# 1_RPi.net
KiCad netlist of a schematic drawn in Altium Designer
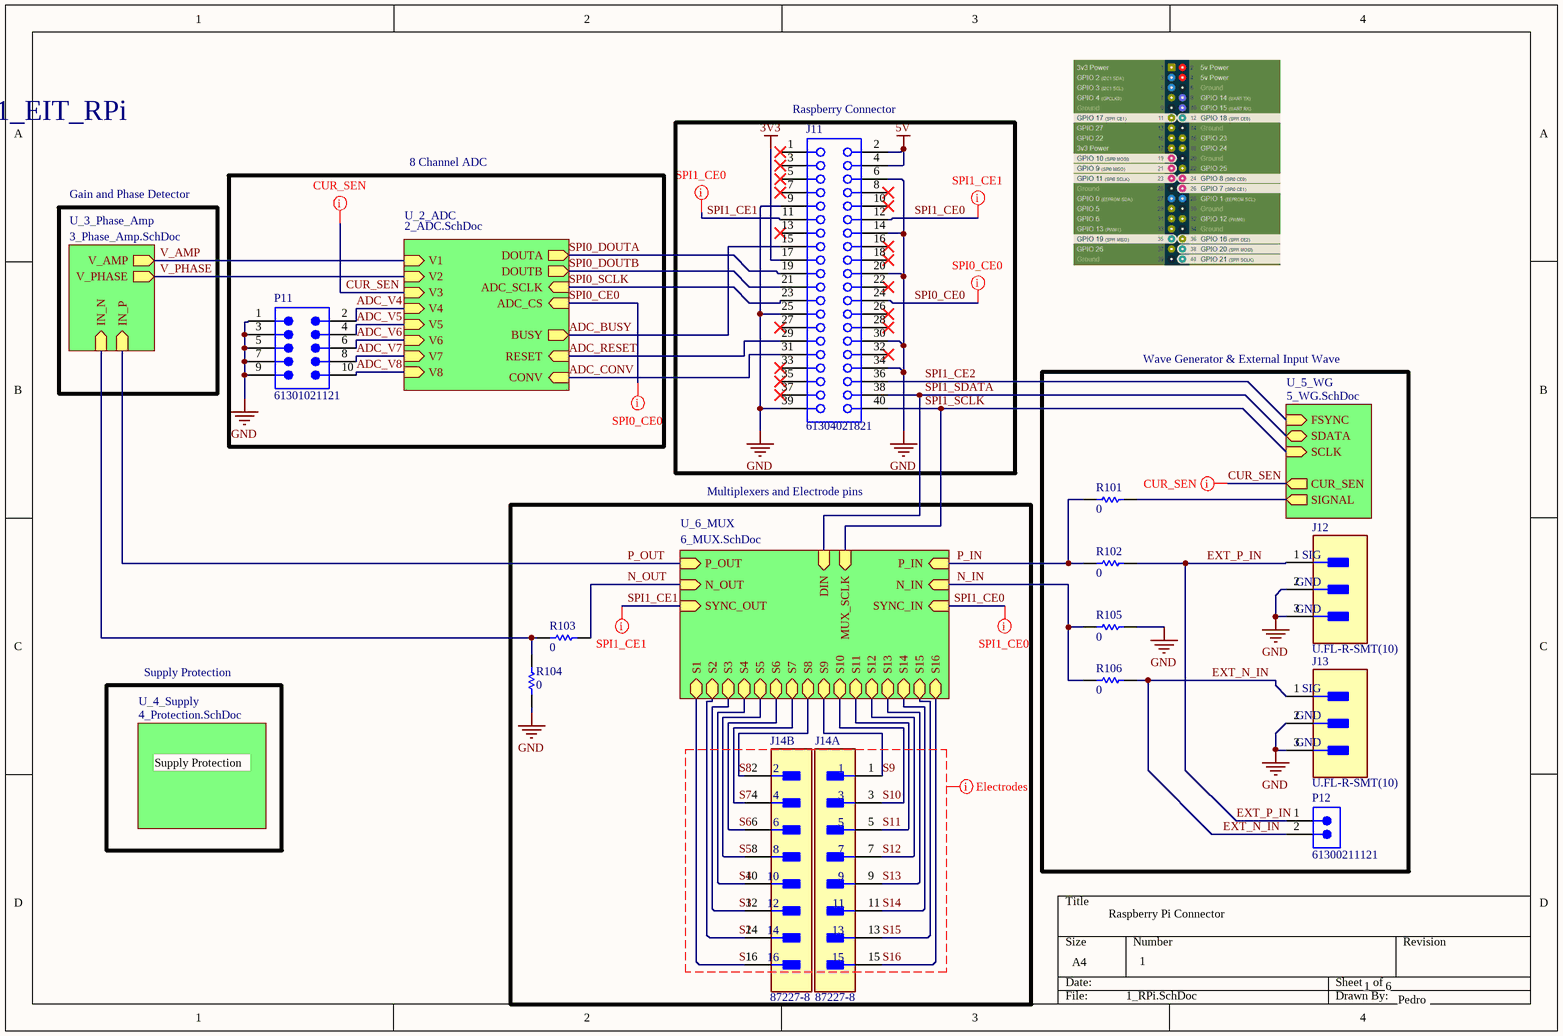
[diagram p0: 1_RPi.SchDoc]

(export (version "E")
  (design (tool "Eeschema 10.0.6"))
  (components
    (comp (ref "J11")
      (value "61304021821")
      (footprint "61304021821")
      (libsource (lib "Altium Content Vault") (part "Header_Female_2R_40P"))
    )
    (comp (ref "J12")
      (value "U.FL-R-SMT(10)")
      (footprint "FP-U_FL-R-SMT_10-MFG")
      (description "CONN U.FL RCPT STR 50 OHM SMD")
      (libsource (lib "RPI_EIT_SchLib") (part "eef6fde44c591823e8076210edfe12f"))
    )
    (comp (ref "J13")
      (value "U.FL-R-SMT(10)")
      (footprint "FP-U_FL-R-SMT_10-MFG")
      (description "CONN U.FL RCPT STR 50 OHM SMD")
      (libsource (lib "RPI_EIT_SchLib") (part "eef6fde44c591823e8076210edfe12f"))
    )
    (comp (ref "J14")
      (value "87227-8")
      (footprint "FP-87227-8-MFG")
      (description "CONN HEADER VERT 16POS 2.54MM")
      (fields
        (field (name "MANUFACTURER") "TE Connectivity")
        (field (name "OCTOPART") "https://octopart.com/87227-8-te+connectivity-39407754")
      )
      (libsource (lib "") (part "4b6d22b45e2f925f038cba5d936fbcc_1"))
    )
    (comp (ref "P11")
      (value "61301021121")
      (footprint "61301021121")
      (libsource (lib "RPI_EIT_SchLib") (part "Header_Male_2R_10P"))
    )
    (comp (ref "P12")
      (value "61300211121")
      (footprint "61300211121")
      (libsource (lib "Altium Content Vault") (part "Header_Male_1R_02P"))
    )
    (comp (ref "R101")
      (value "RC0603JR-070RL")
      (footprint "RESC1608X55X25LL10T15")
      (description "Chip Resistor, 0 Ohm, +/- 5%, 0.1 W, -55 to 155 degC, 0603 (1608 Metric), RoHS, Tape and Reel")
      (fields
        (field (name "TOLERANCE") "5%")
        (field (name "RESISTANCE") "0")
        (field (name "MANUFACTURER") "Yageo")
      )
      (libsource (lib "RPI_EIT_SchLib") (part "RES-2"))
    )
    (comp (ref "R102")
      (value "RC0603JR-070RL")
      (footprint "RESC1608X55X25LL10T15")
      (description "Chip Resistor, 0 Ohm, +/- 5%, 0.1 W, -55 to 155 degC, 0603 (1608 Metric), RoHS, Tape and Reel")
      (fields
        (field (name "TOLERANCE") "5%")
        (field (name "RESISTANCE") "0")
        (field (name "MANUFACTURER") "Yageo")
      )
      (libsource (lib "RPI_EIT_SchLib") (part "RES-2"))
    )
    (comp (ref "R103")
      (value "RC0603JR-070RL")
      (footprint "RESC1608X55X25LL10T15")
      (description "Chip Resistor, 0 Ohm, +/- 5%, 0.1 W, -55 to 155 degC, 0603 (1608 Metric), RoHS, Tape and Reel")
      (fields
        (field (name "TOLERANCE") "5%")
        (field (name "RESISTANCE") "0")
        (field (name "MANUFACTURER") "Yageo")
      )
      (libsource (lib "RPI_EIT_SchLib") (part "RES-2"))
    )
    (comp (ref "R104")
      (value "RC0603JR-070RL")
      (footprint "RESC1608X55X25LL10T15")
      (description "Chip Resistor, 0 Ohm, +/- 5%, 0.1 W, -55 to 155 degC, 0603 (1608 Metric), RoHS, Tape and Reel")
      (fields
        (field (name "TOLERANCE") "5%")
        (field (name "RESISTANCE") "0")
        (field (name "MANUFACTURER") "Yageo")
      )
      (libsource (lib "RPI_EIT_SchLib") (part "RES-2"))
    )
    (comp (ref "R105")
      (value "RC0603JR-070RL")
      (footprint "RESC1608X55X25LL10T15")
      (description "Chip Resistor, 0 Ohm, +/- 5%, 0.1 W, -55 to 155 degC, 0603 (1608 Metric), RoHS, Tape and Reel")
      (fields
        (field (name "TOLERANCE") "5%")
        (field (name "RESISTANCE") "0")
        (field (name "MANUFACTURER") "Yageo")
      )
      (libsource (lib "RPI_EIT_SchLib") (part "RES-2"))
    )
    (comp (ref "R106")
      (value "RC0603JR-070RL")
      (footprint "RESC1608X55X25LL10T15")
      (description "Chip Resistor, 0 Ohm, +/- 5%, 0.1 W, -55 to 155 degC, 0603 (1608 Metric), RoHS, Tape and Reel")
      (fields
        (field (name "TOLERANCE") "5%")
        (field (name "RESISTANCE") "0")
        (field (name "MANUFACTURER") "Yageo")
      )
      (libsource (lib "RPI_EIT_SchLib") (part "RES-2"))
    )
  )
  (nets
    (net (code "1") (name "/ADC_BUSY") (class "Default")
      (node (ref "J11") (pin "15") (pinfunction "15_15") (pintype "passive"))
    )
    (net (code "2") (name "/ADC_CONV") (class "Default")
      (node (ref "J11") (pin "31") (pinfunction "31_31") (pintype "passive"))
    )
    (net (code "3") (name "/ADC_RESET") (class "Default")
      (node (ref "J11") (pin "29") (pinfunction "29_29") (pintype "passive"))
    )
    (net (code "4") (name "/ADC_V4") (class "Default")
      (node (ref "P11") (pin "2") (pinfunction "2_2") (pintype "passive"))
    )
    (net (code "5") (name "/ADC_V5") (class "Default")
      (node (ref "P11") (pin "4") (pinfunction "4_4") (pintype "passive"))
    )
    (net (code "6") (name "/ADC_V6") (class "Default")
      (node (ref "P11") (pin "6") (pinfunction "6_6") (pintype "passive"))
    )
    (net (code "7") (name "/ADC_V7") (class "Default")
      (node (ref "P11") (pin "8") (pinfunction "8_8") (pintype "passive"))
    )
    (net (code "8") (name "/ADC_V8") (class "Default")
      (node (ref "P11") (pin "10") (pinfunction "10_10") (pintype "passive"))
    )
    (net (code "10") (name "/EXT_N_IN") (class "Default")
      (node (ref "J13") (pin "1") (pinfunction "SIG_1") (pintype "passive"))
      (node (ref "P12") (pin "2") (pinfunction "2_2") (pintype "passive"))
      (node (ref "R106") (pin "1") (pinfunction "1_1") (pintype "passive"))
    )
    (net (code "11") (name "/EXT_P_IN") (class "Default")
      (node (ref "J12") (pin "1") (pinfunction "SIG_1") (pintype "passive"))
      (node (ref "P12") (pin "1") (pinfunction "1_1") (pintype "passive"))
      (node (ref "R102") (pin "1") (pinfunction "1_1") (pintype "passive"))
    )
    (net (code "12") (name "/IN_N") (class "Default")
      (node (ref "R103") (pin "2") (pinfunction "2_2") (pintype "passive"))
      (node (ref "R104") (pin "1") (pinfunction "1_1") (pintype "passive"))
    )
    (net (code "13") (name "/N_IN") (class "Default")
      (node (ref "R105") (pin "2") (pinfunction "2_2") (pintype "passive"))
      (node (ref "R106") (pin "2") (pinfunction "2_2") (pintype "passive"))
    )
    (net (code "14") (name "/N_OUT") (class "Default")
      (node (ref "R103") (pin "1") (pinfunction "1_1") (pintype "passive"))
    )
    (net (code "15") (name "/P_IN") (class "Default")
      (node (ref "R101") (pin "2") (pinfunction "2_2") (pintype "passive"))
      (node (ref "R102") (pin "2") (pinfunction "2_2") (pintype "passive"))
    )
    (net (code "17") (name "/S1") (class "Default")
      (node (ref "J14") (pin "16") (pinfunction "16_16") (pintype "passive"))
    )
    (net (code "18") (name "/S2") (class "Default")
      (node (ref "J14") (pin "14") (pinfunction "14_14") (pintype "passive"))
    )
    (net (code "19") (name "/S3") (class "Default")
      (node (ref "J14") (pin "12") (pinfunction "12_12") (pintype "passive"))
    )
    (net (code "20") (name "/S4") (class "Default")
      (node (ref "J14") (pin "10") (pinfunction "10_10") (pintype "passive"))
    )
    (net (code "21") (name "/S5") (class "Default")
      (node (ref "J14") (pin "8") (pinfunction "8_8") (pintype "passive"))
    )
    (net (code "22") (name "/S6") (class "Default")
      (node (ref "J14") (pin "6") (pinfunction "6_6") (pintype "passive"))
    )
    (net (code "23") (name "/S7") (class "Default")
      (node (ref "J14") (pin "4") (pinfunction "4_4") (pintype "passive"))
    )
    (net (code "24") (name "/S8") (class "Default")
      (node (ref "J14") (pin "2") (pinfunction "2_2") (pintype "passive"))
    )
    (net (code "25") (name "/S9") (class "Default")
      (node (ref "J14") (pin "1") (pinfunction "1_1") (pintype "passive"))
    )
    (net (code "26") (name "/S10") (class "Default")
      (node (ref "J14") (pin "3") (pinfunction "3_3") (pintype "passive"))
    )
    (net (code "27") (name "/S11") (class "Default")
      (node (ref "J14") (pin "5") (pinfunction "5_5") (pintype "passive"))
    )
    (net (code "28") (name "/S12") (class "Default")
      (node (ref "J14") (pin "7") (pinfunction "7_7") (pintype "passive"))
    )
    (net (code "29") (name "/S13") (class "Default")
      (node (ref "J14") (pin "9") (pinfunction "9_9") (pintype "passive"))
    )
    (net (code "30") (name "/S14") (class "Default")
      (node (ref "J14") (pin "11") (pinfunction "11_11") (pintype "passive"))
    )
    (net (code "31") (name "/S15") (class "Default")
      (node (ref "J14") (pin "13") (pinfunction "13_13") (pintype "passive"))
    )
    (net (code "32") (name "/S16") (class "Default")
      (node (ref "J14") (pin "15") (pinfunction "15_15") (pintype "passive"))
    )
    (net (code "33") (name "/SIGNAL") (class "Default")
      (node (ref "R101") (pin "1") (pinfunction "1_1") (pintype "passive"))
    )
    (net (code "34") (name "/SPI0_CE0") (class "Default")
      (node (ref "J11") (pin "24") (pinfunction "24_24") (pintype "passive"))
    )
    (net (code "35") (name "/SPI0_DOUTA") (class "Default")
      (node (ref "J11") (pin "19") (pinfunction "19_19") (pintype "passive"))
    )
    (net (code "36") (name "/SPI0_DOUTB") (class "Default")
      (node (ref "J11") (pin "21") (pinfunction "21_21") (pintype "passive"))
    )
    (net (code "37") (name "/SPI0_SCLK") (class "Default")
      (node (ref "J11") (pin "23") (pinfunction "23_23") (pintype "passive"))
    )
    (net (code "38") (name "/SPI1_CE0") (class "Default")
      (node (ref "J11") (pin "12") (pinfunction "12_12") (pintype "passive"))
    )
    (net (code "39") (name "/SPI1_CE1") (class "Default")
      (node (ref "J11") (pin "11") (pinfunction "11_11") (pintype "passive"))
    )
    (net (code "40") (name "/SPI1_CE2") (class "Default")
      (node (ref "J11") (pin "36") (pinfunction "36_36") (pintype "passive"))
    )
    (net (code "41") (name "/SPI1_SCLK") (class "Default")
      (node (ref "J11") (pin "40") (pinfunction "40_40") (pintype "passive"))
    )
    (net (code "42") (name "/SPI1_SDATA") (class "Default")
      (node (ref "J11") (pin "38") (pinfunction "38_38") (pintype "passive"))
    )
    (net (code "45") (name "3V3") (class "Default")
      (node (ref "J11") (pin "17") (pinfunction "17_17") (pintype "passive"))
    )
    (net (code "46") (name "5V") (class "Default")
      (node (ref "J11") (pin "2") (pinfunction "2_2") (pintype "passive"))
      (node (ref "J11") (pin "4") (pinfunction "4_4") (pintype "passive"))
    )
    (net (code "47") (name "GND") (class "Default")
      (node (ref "J11") (pin "14") (pinfunction "14_14") (pintype "passive"))
      (node (ref "J11") (pin "20") (pinfunction "20_20") (pintype "passive"))
      (node (ref "J11") (pin "25") (pinfunction "25_25") (pintype "passive"))
      (node (ref "J11") (pin "30") (pinfunction "30_30") (pintype "passive"))
      (node (ref "J11") (pin "34") (pinfunction "34_34") (pintype "passive"))
      (node (ref "J11") (pin "39") (pinfunction "39_39") (pintype "passive"))
      (node (ref "J11") (pin "6") (pinfunction "6_6") (pintype "passive"))
      (node (ref "J11") (pin "9") (pinfunction "9_9") (pintype "passive"))
      (node (ref "J12") (pin "2") (pinfunction "GND_2") (pintype "power_in"))
      (node (ref "J12") (pin "3") (pinfunction "GND_3") (pintype "power_in"))
      (node (ref "J13") (pin "2") (pinfunction "GND_2") (pintype "power_in"))
      (node (ref "J13") (pin "3") (pinfunction "GND_3") (pintype "power_in"))
      (node (ref "P11") (pin "1") (pinfunction "1_1") (pintype "passive"))
      (node (ref "P11") (pin "3") (pinfunction "3_3") (pintype "passive"))
      (node (ref "P11") (pin "5") (pinfunction "5_5") (pintype "passive"))
      (node (ref "P11") (pin "7") (pinfunction "7_7") (pintype "passive"))
      (node (ref "P11") (pin "9") (pinfunction "9_9") (pintype "passive"))
      (node (ref "R104") (pin "2") (pinfunction "2_2") (pintype "passive"))
      (node (ref "R105") (pin "1") (pinfunction "1_1") (pintype "passive"))
    )
    (net (code "48") (name "unconnected-(J11-Pad1)") (class "Default")
      (node (ref "J11") (pin "1") (pinfunction "1_1") (pintype "passive+no_connect"))
    )
    (net (code "49") (name "unconnected-(J11-Pad3)") (class "Default")
      (node (ref "J11") (pin "3") (pinfunction "3_3") (pintype "passive+no_connect"))
    )
    (net (code "50") (name "unconnected-(J11-Pad5)") (class "Default")
      (node (ref "J11") (pin "5") (pinfunction "5_5") (pintype "passive+no_connect"))
    )
    (net (code "51") (name "unconnected-(J11-Pad7)") (class "Default")
      (node (ref "J11") (pin "7") (pinfunction "7_7") (pintype "passive+no_connect"))
    )
    (net (code "52") (name "unconnected-(J11-Pad8)") (class "Default")
      (node (ref "J11") (pin "8") (pinfunction "8_8") (pintype "passive+no_connect"))
    )
    (net (code "53") (name "unconnected-(J11-Pad10)") (class "Default")
      (node (ref "J11") (pin "10") (pinfunction "10_10") (pintype "passive+no_connect"))
    )
    (net (code "54") (name "unconnected-(J11-Pad13)") (class "Default")
      (node (ref "J11") (pin "13") (pinfunction "13_13") (pintype "passive+no_connect"))
    )
    (net (code "55") (name "unconnected-(J11-Pad16)") (class "Default")
      (node (ref "J11") (pin "16") (pinfunction "16_16") (pintype "passive+no_connect"))
    )
    (net (code "56") (name "unconnected-(J11-Pad18)") (class "Default")
      (node (ref "J11") (pin "18") (pinfunction "18_18") (pintype "passive+no_connect"))
    )
    (net (code "57") (name "unconnected-(J11-Pad22)") (class "Default")
      (node (ref "J11") (pin "22") (pinfunction "22_22") (pintype "passive+no_connect"))
    )
    (net (code "58") (name "unconnected-(J11-Pad26)") (class "Default")
      (node (ref "J11") (pin "26") (pinfunction "26_26") (pintype "passive+no_connect"))
    )
    (net (code "59") (name "unconnected-(J11-Pad27)") (class "Default")
      (node (ref "J11") (pin "27") (pinfunction "27_27") (pintype "passive+no_connect"))
    )
    (net (code "60") (name "unconnected-(J11-Pad28)") (class "Default")
      (node (ref "J11") (pin "28") (pinfunction "28_28") (pintype "passive+no_connect"))
    )
    (net (code "61") (name "unconnected-(J11-Pad32)") (class "Default")
      (node (ref "J11") (pin "32") (pinfunction "32_32") (pintype "passive+no_connect"))
    )
    (net (code "62") (name "unconnected-(J11-Pad33)") (class "Default")
      (node (ref "J11") (pin "33") (pinfunction "33_33") (pintype "passive+no_connect"))
    )
    (net (code "63") (name "unconnected-(J11-Pad35)") (class "Default")
      (node (ref "J11") (pin "35") (pinfunction "35_35") (pintype "passive+no_connect"))
    )
    (net (code "64") (name "unconnected-(J11-Pad37)") (class "Default")
      (node (ref "J11") (pin "37") (pinfunction "37_37") (pintype "passive+no_connect"))
    )
  )
)
